# CM_Title.net
KiCad netlist of a schematic drawn in Altium Designer
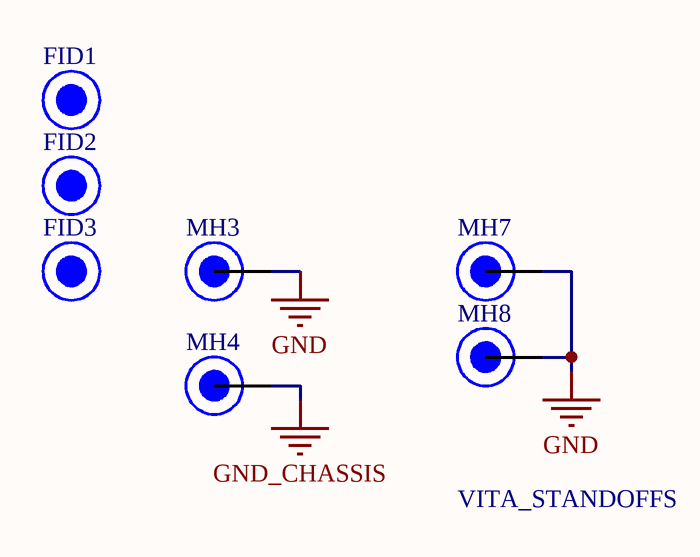
[diagram p0: CM_Title.SchDoc]

(export (version "E")
  (design (tool "Eeschema 10.0.6"))
  (components
    (comp (ref "FID1")
      (value "Fiducial 1mm")
      (footprint "FID_1MM")
      (description "FID - 1MM")
      (fields (field (name "CREATEDBY") "Jonathan Bouchard") (field (name "VERIFIEDBY") "Alexandre Imbeault"))
      (libsource (lib "S7CAS_Lib2019_REV1_00") (part "FID_1MM"))
    )
    (comp (ref "FID2")
      (value "Fiducial 1mm")
      (footprint "FID_1MM")
      (description "FID - 1MM")
      (fields (field (name "CREATEDBY") "Jonathan Bouchard") (field (name "VERIFIEDBY") "Alexandre Imbeault"))
      (libsource (lib "S7CAS_Lib2019_REV1_00") (part "FID_1MM"))
    )
    (comp (ref "FID3")
      (value "Fiducial 1mm")
      (footprint "FID_1MM")
      (description "FID - 1MM")
      (fields (field (name "CREATEDBY") "Jonathan Bouchard") (field (name "VERIFIEDBY") "Alexandre Imbeault"))
      (libsource (lib "S7CAS_Lib2019_REV1_00") (part "FID_1MM"))
    )
    (comp (ref "MH3")
      (value "Mounting Hole 6-32")
      (footprint "MH_ENG_6-32")
      (description "MH - Mounting Hole 6-32")
      (fields (field (name "CREATEDBY") "Jonathan Bouchard") (field (name "VERIFIEDBY") "Alexandre Imbeault"))
      (libsource (lib "S7CAS_Lib2019_REV1_00") (part "MH_6-32"))
    )
    (comp (ref "MH4")
      (value "Mounting Hole 6-32")
      (footprint "MH_ENG_6-32")
      (description "MH - Mounting Hole 6-32")
      (fields (field (name "CREATEDBY") "Jonathan Bouchard") (field (name "VERIFIEDBY") "Alexandre Imbeault"))
      (libsource (lib "S7CAS_Lib2019_REV1_00") (part "MH_6-32"))
    )
    (comp (ref "MH7")
      (value "2.7 mm")
      (footprint "MH_ENG_6-32")
      (description "MH - Mounting Hole 6-32")
      (fields (field (name "CREATEDBY") "Jonathan Bouchard") (field (name "VERIFIEDBY") "Alexandre Imbeault"))
      (libsource (lib "S7CAS_Lib2019_REV1_00") (part "MH_6-32"))
    )
    (comp (ref "MH8")
      (value "2.7 mm")
      (footprint "MH_ENG_6-32")
      (description "MH - Mounting Hole 6-32")
      (fields (field (name "CREATEDBY") "Jonathan Bouchard") (field (name "VERIFIEDBY") "Alexandre Imbeault"))
      (libsource (lib "S7CAS_Lib2019_REV1_00") (part "MH_6-32"))
    )
  )
  (nets
    (net (code "1") (name "GND") (class "Default")
      (node (ref "MH3") (pin "1") (pinfunction "1_1") (pintype "passive"))
      (node (ref "MH7") (pin "1") (pinfunction "1_1") (pintype "passive"))
      (node (ref "MH8") (pin "1") (pinfunction "1_1") (pintype "passive"))
    )
    (net (code "2") (name "GND_CHASSIS") (class "Default")
      (node (ref "MH4") (pin "1") (pinfunction "1_1") (pintype "passive"))
    )
  )
)
